# 03-.net
KiCad netlist of a schematic drawn in Altium Designer
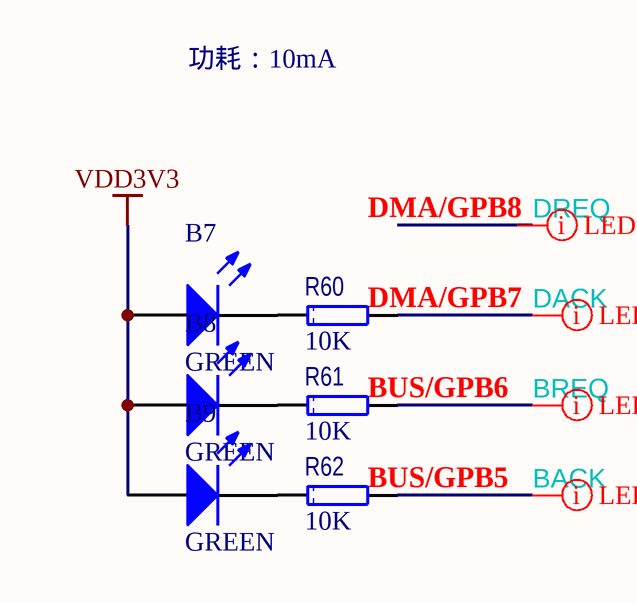
[diagram p0: 03-指示灯.SchDoc]

(export (version "E")
  (design (tool "Eeschema 10.0.6"))
  (components
    (comp (ref "B7")
      (value "GREEN")
      (footprint "0805LED")
      (description "Typical RED, GREEN, YELLOW, AMBER GaAs LED")
      (fields (field (name "PUBLISHER") "Altium Limited"))
      (libsource (lib "Miscellaneous Devices") (part "LED2"))
    )
    (comp (ref "B8")
      (value "GREEN")
      (footprint "0805LED")
      (description "Typical RED, GREEN, YELLOW, AMBER GaAs LED")
      (fields (field (name "PUBLISHER") "Altium Limited"))
      (libsource (lib "Miscellaneous Devices") (part "LED2"))
    )
    (comp (ref "B9")
      (value "GREEN")
      (footprint "0805LED")
      (description "Typical RED, GREEN, YELLOW, AMBER GaAs LED")
      (fields (field (name "PUBLISHER") "Altium Limited"))
      (libsource (lib "Miscellaneous Devices") (part "LED2"))
    )
    (comp (ref "R60")
      (value "10K")
      (footprint "1608[0603]R")
      (description "厚膜电阻器 - SMD 1/10watt 10Kohms 1%")
      (fields
        (field (name "MANUFACTURER") "Vishay / Dale")
        (field (name "MANUFACTURER PART NUMBER") "CRCW060310K0FKEA")
      )
      (libsource (lib "10K 1%") (part "RES"))
    )
    (comp (ref "R61")
      (value "10K")
      (footprint "1608[0603]R")
      (description "厚膜电阻器 - SMD 1/10watt 10Kohms 1%")
      (fields
        (field (name "MANUFACTURER") "Vishay / Dale")
        (field (name "MANUFACTURER PART NUMBER") "CRCW060310K0FKEA")
      )
      (libsource (lib "10K 1%") (part "RES"))
    )
    (comp (ref "R62")
      (value "10K")
      (footprint "1608[0603]R")
      (description "厚膜电阻器 - SMD 1/10watt 10Kohms 1%")
      (fields
        (field (name "MANUFACTURER") "Vishay / Dale")
        (field (name "MANUFACTURER PART NUMBER") "CRCW060310K0FKEA")
      )
      (libsource (lib "10K 1%") (part "RES"))
    )
  )
  (nets
    (net (code "1") (name "/BACK") (class "Default")
      (node (ref "R62") (pin "2") (pinfunction "2_2") (pintype "passive"))
    )
    (net (code "2") (name "/BREQ") (class "Default")
      (node (ref "R61") (pin "2") (pinfunction "2_2") (pintype "passive"))
    )
    (net (code "3") (name "/DACK") (class "Default")
      (node (ref "R60") (pin "2") (pinfunction "2_2") (pintype "passive"))
    )
    (net (code "5") (name "Net-(B7-K)") (class "Default")
      (node (ref "B7") (pin "2") (pinfunction "K_2") (pintype "passive"))
      (node (ref "R60") (pin "1") (pinfunction "1_1") (pintype "passive"))
    )
    (net (code "6") (name "Net-(B8-K)") (class "Default")
      (node (ref "B8") (pin "2") (pinfunction "K_2") (pintype "passive"))
      (node (ref "R61") (pin "1") (pinfunction "1_1") (pintype "passive"))
    )
    (net (code "7") (name "Net-(B9-K)") (class "Default")
      (node (ref "B9") (pin "2") (pinfunction "K_2") (pintype "passive"))
      (node (ref "R62") (pin "1") (pinfunction "1_1") (pintype "passive"))
    )
    (net (code "8") (name "VDD3V3") (class "Default")
      (node (ref "B7") (pin "1") (pinfunction "A_1") (pintype "passive"))
      (node (ref "B8") (pin "1") (pinfunction "A_1") (pintype "passive"))
      (node (ref "B9") (pin "1") (pinfunction "A_1") (pintype "passive"))
    )
  )
)
